# PowerPlan.net
KiCad netlist of a schematic drawn in Altium Designer
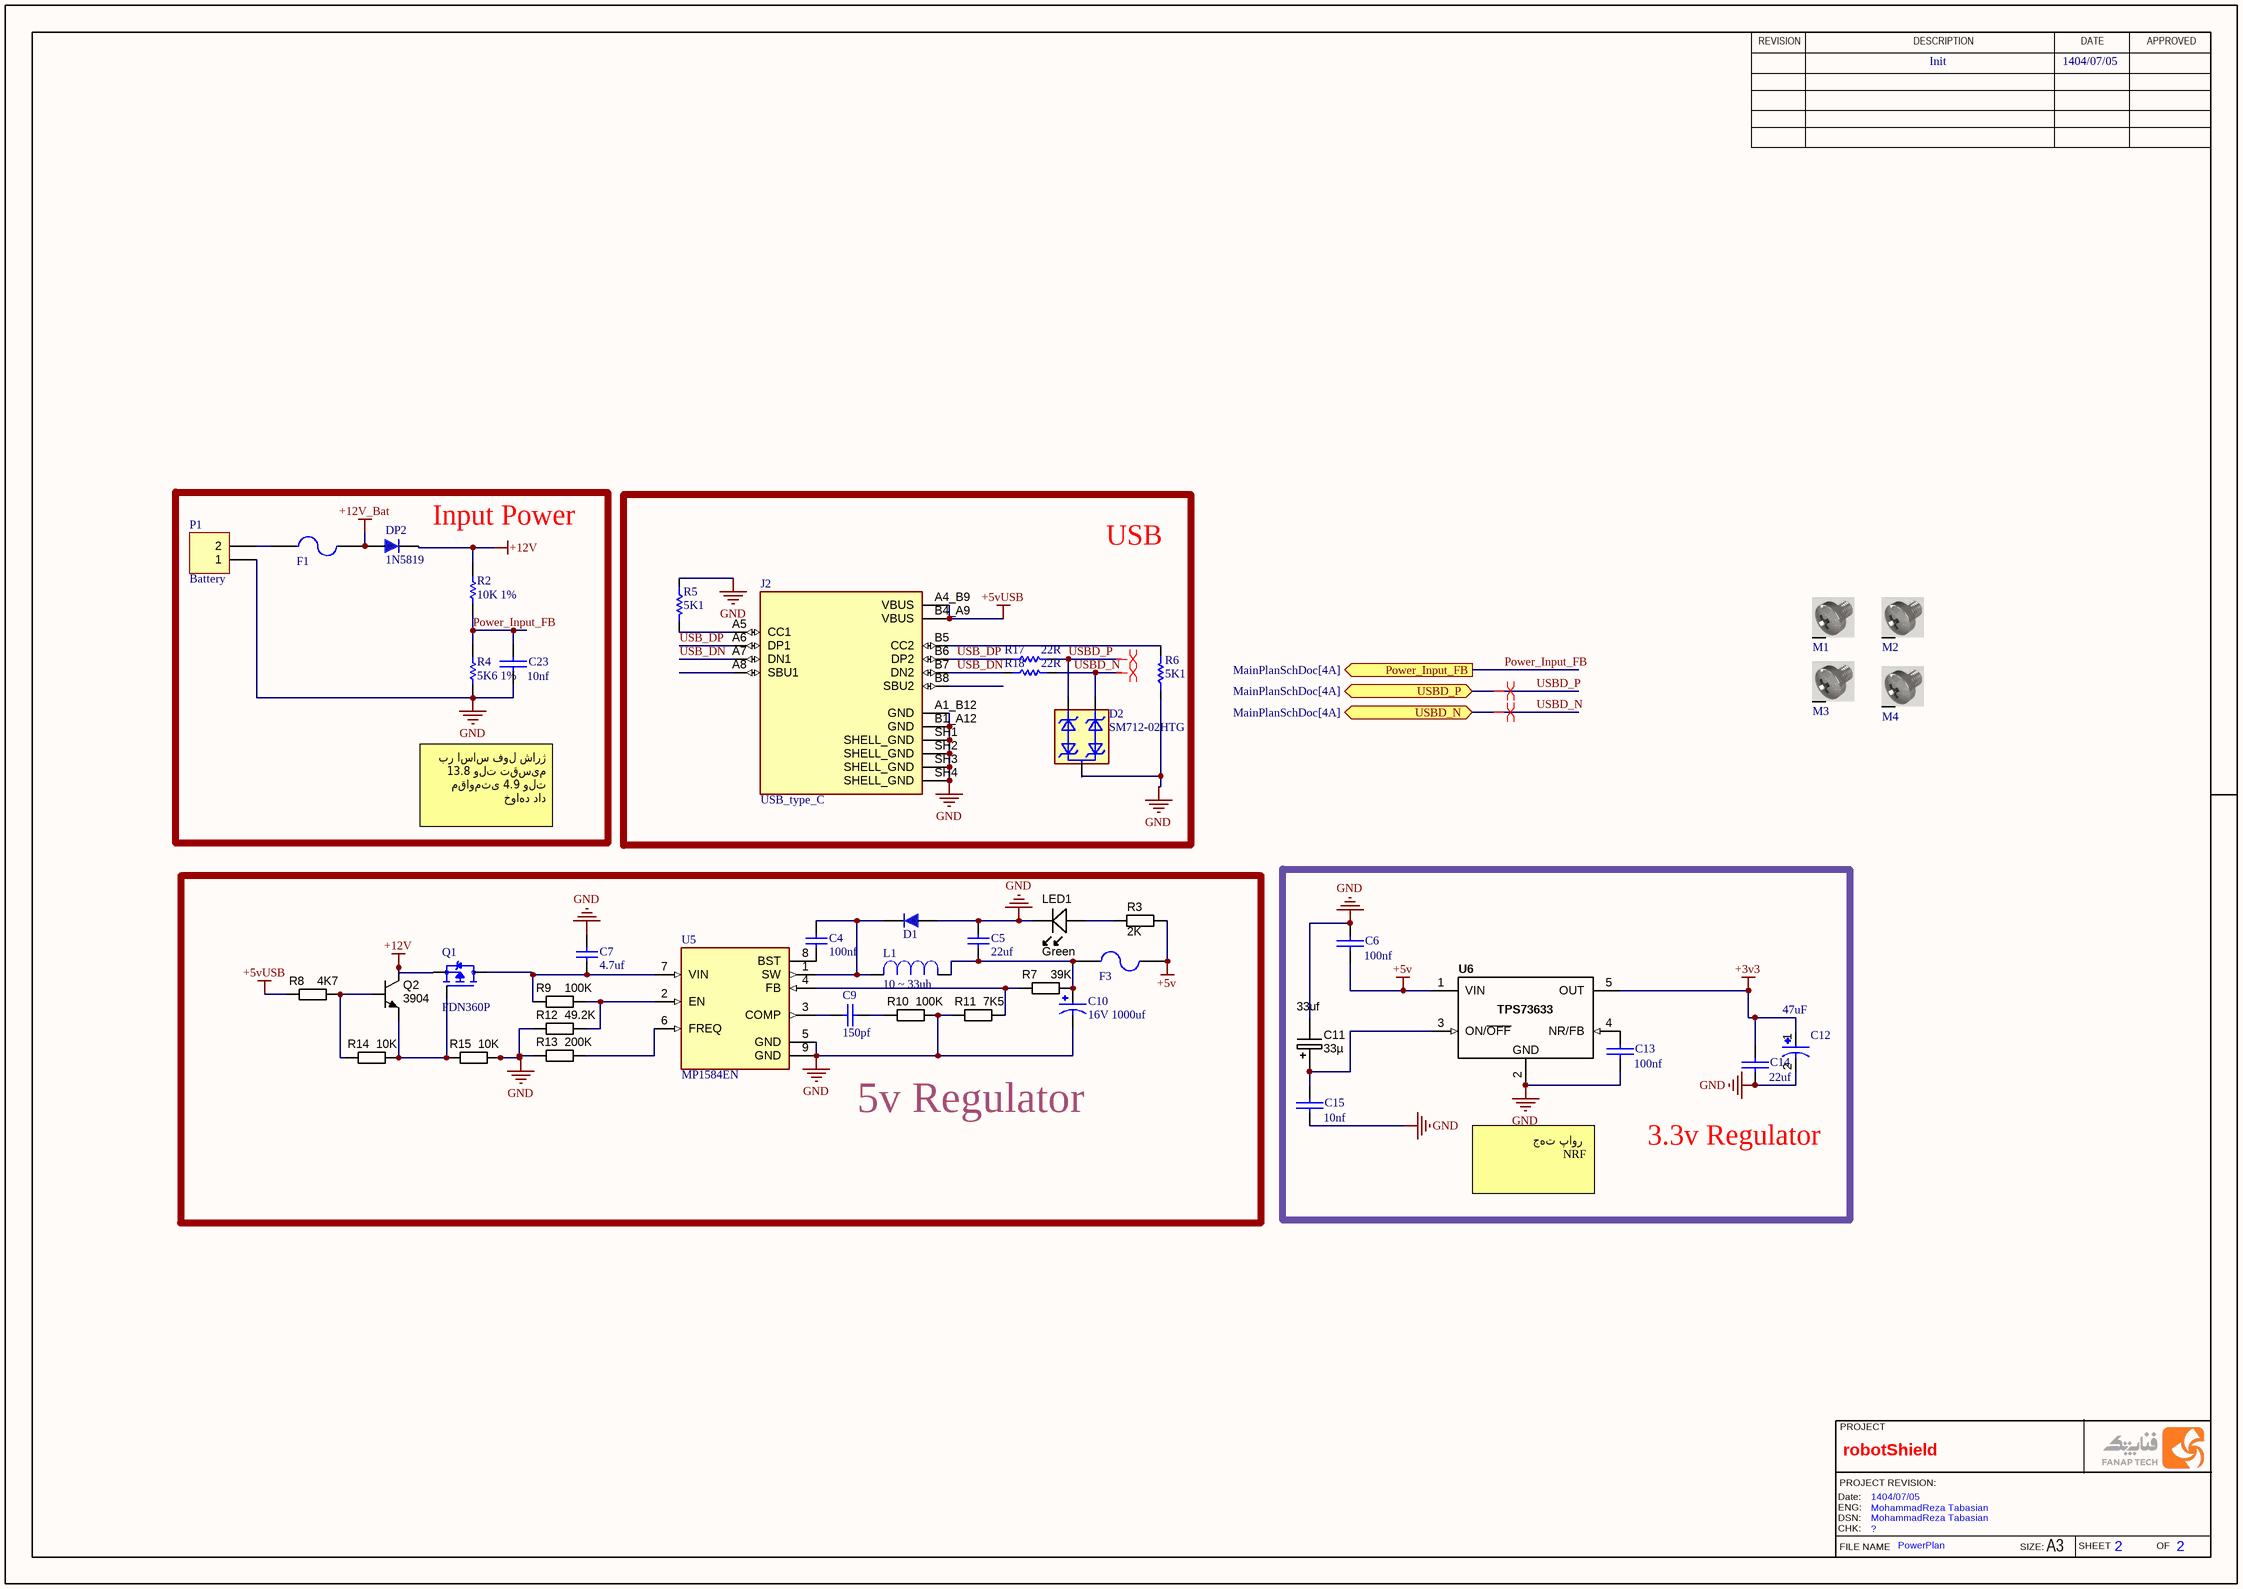
[diagram p0: PowerPlan.SchDoc]

(export (version "E")
  (design (tool "Eeschema 10.0.6"))
  (components
    (comp (ref "C4")
      (value "100nf")
      (footprint "C0805")
      (description "CAP 0805")
      (fields (field (name "DESIGNER") "Abbas Basereh"))
      (libsource (lib "Altium") (part "CAP SMD 0805"))
    )
    (comp (ref "C5")
      (value "22uf")
      (footprint "C1206")
      (description "CAP 1206")
      (fields (field (name "DESIGNER") "Abbas Basereh"))
      (libsource (lib "Altium") (part "CAP SMD 1206"))
    )
    (comp (ref "C6")
      (value "100nf")
      (footprint "C0805")
      (description "Bipolar Capacitor")
      (fields (field (name "VOLTAGE") "100V") (field (name "DESIGNER") "Saeid Jorablo"))
      (libsource (lib "My_Library") (part "Cap-Bipolar"))
    )
    (comp (ref "C7")
      (value "4.7uf")
      (footprint "C1206")
      (description "CAP 1206")
      (fields (field (name "DESIGNER") "Abbas Basereh"))
      (libsource (lib "Altium") (part "CAP SMD 1206"))
    )
    (comp (ref "C9")
      (value "150pf")
      (footprint "C0805")
      (description "CAP 0805")
      (fields (field (name "DESIGNER") "Abbas Basereh"))
      (libsource (lib "Altium") (part "CAP SMD 0805"))
    )
    (comp (ref "C10")
      (value "16V 1000uf")
      (footprint "CAP_SMD13*13")
      (description "CAP ALUM 470UF 20% 35V SMD")
      (fields (field (name "MF") "Panasonic Electronic Components") (field (name "MP") "EEE-FN1V471UP"))
      (libsource (lib "TB_LIB") (part "CAP_SMD13*13"))
    )
    (comp (ref "C11")
      (value "33uf")
      (footprint "CAPMP6032X280N")
      (description "Capacitor SMD Tantalum 33uF 10% 6.3V 3216-18")
      (fields (field (name "TOLERANCE") "±10%") (field (name "ALTIUM_VALUE") "33µ"))
      (libsource (lib "Utiliti_Library") (part "CAPT_33u_3216_6V3"))
    )
    (comp (ref "C12")
      (value "47uF")
      (footprint "CAPMP7343X430N")
      (description "Cap, Tant, 470uf, 10v, Case x")
      (fields (field (name "MP") "T541X107M025AH6510") (field (name "MF") "KEMET"))
      (libsource (lib "TB_LIB") (part "T541X107M025AH6510"))
    )
    (comp (ref "C13")
      (value "100nf")
      (footprint "C0805")
      (description "Bipolar Capacitor")
      (fields (field (name "VOLTAGE") "100V") (field (name "DESIGNER") "Saeid Jorablo"))
      (libsource (lib "My_Library") (part "Cap-Bipolar"))
    )
    (comp (ref "C14")
      (value "22uf")
      (footprint "C1206")
      (description "Bipolar Capacitor")
      (fields (field (name "VOLTAGE") "100V") (field (name "DESIGNER") "Saeid Jorablo"))
      (libsource (lib "My_Library") (part "Cap-Bipolar"))
    )
    (comp (ref "C15")
      (value "10nf")
      (footprint "C0805")
      (description "Bipolar Capacitor")
      (fields (field (name "VOLTAGE") "100V") (field (name "DESIGNER") "Saeid Jorablo"))
      (libsource (lib "My_Library") (part "Cap-Bipolar"))
    )
    (comp (ref "C23")
      (value "10nf")
      (footprint "C0805")
      (description "Bipolar Capacitor")
      (fields (field (name "VOLTAGE") "100V") (field (name "DESIGNER") "Saeid Jorablo"))
      (libsource (lib "My_Library") (part "Cap-Bipolar"))
    )
    (comp (ref "D1")
      (value "SS34")
      (footprint "DIOM4629X24N")
      (description "Standard Rectifiers")
      (fields (field (name "MANUFACTURER") "DC COMPONENTS") (field (name "DESIGNER") "Abbas Basereh"))
      (libsource (lib "Altium") (part "1n4007 SMD M7"))
    )
    (comp (ref "D2")
      (value "SM712-02HTG")
      (footprint "SOT23")
      (fields (field (name "MF") "Littelfuse"))
      (libsource (lib "TB_LIB") (part "SM712-02HTG"))
    )
    (comp (ref "DP2")
      (value "1N5819")
      (footprint "430X270D")
      (description "Schottkey Rectifiers")
      (fields (field (name "DESIGNER") "Abbas Basereh"))
      (libsource (lib "Altium") (part "1N5819"))
    )
    (comp (ref "F1")
      (value "F300ma")
      (footprint "1206 FUSE")
      (description "SMD Fuses 1206")
      (fields (field (name "DESIGNER") "Abbas Basereh"))
      (libsource (lib "Altium") (part "Fuse SMD1206"))
    )
    (comp (ref "F3")
      (value "F300ma")
      (footprint "1206 FUSE")
      (description "SMD Fuses 1206")
      (fields (field (name "DESIGNER") "Abbas Basereh"))
      (libsource (lib "Altium") (part "Fuse SMD1206"))
    )
    (comp (ref "J2")
      (value "USB_type_C")
      (footprint "USB_type_C")
      (fields (field (name "MF") "{'manufacturer': u'GCT'}") (field (name "MP") "USB4105-GF-A"))
      (libsource (lib "TB_LIB") (part "USB_type_C"))
    )
    (comp (ref "L1")
      (value "10 ~ 33uh")
      (footprint "IND_7*7")
      (description "100ÂµH Shielded Wirewound Inductor 1.96A 163mOhm Nonstandard")
      (fields (field (name "MF") "Eaton") (field (name "MP") "DR127-101-R"))
      (libsource (lib "TB_LIB") (part "Inductor 100uh"))
    )
    (comp (ref "LED1")
      (value "LED")
      (footprint "LED-0805-K")
      (description "LED, 0805 SMD, Green")
      (fields (field (name "COLOR") "Green"))
      (libsource (lib "Utiliti_Library") (part "LED_SMD_Green_0805_6mcd"))
    )
    (comp (ref "M1")
      (value "Screw")
      (footprint "Board Screw_No Silk")
      (description "Board Screw With Spacer")
      (libsource (lib "My Library") (part "Board Screw"))
    )
    (comp (ref "M2")
      (value "Screw")
      (footprint "Board Screw_No Silk")
      (description "Board Screw With Spacer")
      (libsource (lib "My Library") (part "Board Screw"))
    )
    (comp (ref "M3")
      (value "Screw")
      (footprint "Board Screw_No Silk")
      (description "Board Screw With Spacer")
      (libsource (lib "My Library") (part "Board Screw"))
    )
    (comp (ref "M4")
      (value "Screw")
      (footprint "Board Screw_No Silk")
      (description "Board Screw With Spacer")
      (libsource (lib "My Library") (part "Board Screw"))
    )
    (comp (ref "P1")
      (value "Battery")
      (footprint "HDR1X2")
      (description "Header, 2-Pin")
      (fields (field (name "PUBLISHER") "Altium Limited"))
      (libsource (lib "Altium") (part "Header 2"))
    )
    (comp (ref "Q1")
      (value "FDN360P")
      (footprint "SOT95P251X112-3N")
      (description "P-Channel 30V 2A (Ta) 500mW (Ta) Surface Mount SuperSOT-3")
      (fields (field (name "MF") "ON"))
      (libsource (lib "TB_LIB") (part "FDN360P"))
    )
    (comp (ref "Q2")
      (value "3904")
      (footprint "SOT23-3")
      (description "Transistor SMD NPN 40V 0.2A 250mW SOT-23")
      (fields (field (name "MANUFACTURER PART NUMBER 1") "3904"))
      (libsource (lib "Utiliti_Library") (part "NPN_MMBT3904"))
    )
    (comp (ref "R2")
      (value "10K 1%")
      (footprint "C0805")
      (description "RES 1206")
      (fields (field (name "DESIGNER") "Abbas Basereh"))
      (libsource (lib "2017AbbasBasereh9365731239 -ver1") (part "RES 1206 0.25W"))
    )
    (comp (ref "R3")
      (value "2K")
      (footprint "C0805")
      (description "Resistor SMD 0805")
      (libsource (lib "") (part "RES_0R_0805_1"))
    )
    (comp (ref "R4")
      (value "5K6 1%")
      (footprint "C0805")
      (description "RES 1206")
      (fields (field (name "DESIGNER") "Abbas Basereh"))
      (libsource (lib "2017AbbasBasereh9365731239 -ver1") (part "RES 1206 0.25W"))
    )
    (comp (ref "R5")
      (value "5K1")
      (footprint "C0805")
      (description "Resistor")
      (libsource (lib "My_Library") (part "Resistor"))
    )
    (comp (ref "R6")
      (value "5K1")
      (footprint "C0805")
      (description "Resistor")
      (libsource (lib "My_Library") (part "Resistor"))
    )
    (comp (ref "R7")
      (value "39K")
      (footprint "C0805")
      (description "Resistor SMD 0805")
      (libsource (lib "Utiliti_Library") (part "RES_0R_0805"))
    )
    (comp (ref "R8")
      (value "4K7")
      (footprint "C0805")
      (description "Resistor SMD 0805")
      (libsource (lib "Utiliti_Library") (part "RES_0R_0805"))
    )
    (comp (ref "R9")
      (value "100K")
      (footprint "C0805")
      (description "Resistor SMD 0805")
      (libsource (lib "Utiliti_Library") (part "RES_0R_0805"))
    )
    (comp (ref "R10")
      (value "100K")
      (footprint "C0805")
      (description "Resistor SMD 0805")
      (libsource (lib "Utiliti_Library") (part "RES_0R_0805"))
    )
    (comp (ref "R11")
      (value "7K5")
      (footprint "C0805")
      (description "Resistor SMD 0805")
      (libsource (lib "Utiliti_Library") (part "RES_0R_0805"))
    )
    (comp (ref "R12")
      (value "49.2K")
      (footprint "C0805")
      (description "Resistor SMD 0805")
      (libsource (lib "Utiliti_Library") (part "RES_0R_0805"))
    )
    (comp (ref "R13")
      (value "200K")
      (footprint "C0805")
      (description "Resistor SMD 0805")
      (libsource (lib "Utiliti_Library") (part "RES_0R_0805"))
    )
    (comp (ref "R14")
      (value "10K")
      (footprint "C0805")
      (description "Resistor SMD 0805")
      (libsource (lib "Utiliti_Library") (part "RES_0R_0805"))
    )
    (comp (ref "R15")
      (value "10K")
      (footprint "C0805")
      (description "Resistor SMD 0805")
      (libsource (lib "Utiliti_Library") (part "RES_0R_0805"))
    )
    (comp (ref "R17")
      (value "22R")
      (footprint "C0805")
      (description "Resistor")
      (libsource (lib "My_Library") (part "Resistor"))
    )
    (comp (ref "R18")
      (value "22R")
      (footprint "C0805")
      (description "Resistor")
      (libsource (lib "My_Library") (part "Resistor"))
    )
    (comp (ref "U5")
      (value "MP1584EN")
      (footprint "SOIC_8P_127P600X170-9N")
      (fields (field (name "MF") "Monolithic Power"))
      (libsource (lib "TB_LIB") (part "MP1584EN"))
    )
    (comp (ref "U6")
      (value "3.3V")
      (footprint "SOT23-5")
      (description "IC LDO Regulator 3.3V 400mA SOT23-5 SMD")
      (fields (field (name "TOLERANCE") "±0.5%"))
      (libsource (lib "Utiliti_Library") (part "LinREG_3V3_400mA_TPS73633DBV"))
    )
  )
  (nets
    (net (code "1") (name "+3v3") (class "Default")
      (node (ref "C12") (pin "1") (pinfunction "1_1") (pintype "passive"))
      (node (ref "C14") (pin "1") (pinfunction "+_1") (pintype "passive"))
      (node (ref "U6") (pin "5") (pinfunction "OUT_5") (pintype "power_in"))
    )
    (net (code "2") (name "+5v") (class "Default")
      (node (ref "C6") (pin "2") (pinfunction "-_2") (pintype "passive"))
      (node (ref "F3") (pin "2") (pinfunction "2_2") (pintype "passive"))
      (node (ref "R3") (pin "1") (pinfunction "1_1") (pintype "passive"))
      (node (ref "U6") (pin "1") (pinfunction "VIN_1") (pintype "power_in"))
    )
    (net (code "3") (name "+5vUSB") (class "Default")
      (node (ref "J2") (pin "A4_B9") (pinfunction "VBUS_A4_B9") (pintype "power_in"))
      (node (ref "J2") (pin "B4_A9") (pinfunction "VBUS_B4_A9") (pintype "power_in"))
      (node (ref "R8") (pin "1") (pinfunction "1_1") (pintype "passive"))
    )
    (net (code "4") (name "+12V") (class "Default")
      (node (ref "DP2") (pin "2") (pintype "passive"))
      (node (ref "Q1") (pin "2") (pinfunction "S_2") (pintype "passive"))
      (node (ref "Q2") (pin "3") (pinfunction "C_3") (pintype "passive"))
      (node (ref "R2") (pin "2") (pinfunction "2_2") (pintype "passive"))
    )
    (net (code "5") (name "+12V_Bat") (class "Default")
      (node (ref "DP2") (pin "1") (pintype "passive"))
      (node (ref "F1") (pin "2") (pinfunction "2_2") (pintype "passive"))
    )
    (net (code "6") (name "/Power_Input_FB") (class "Default")
      (node (ref "C23") (pin "1") (pinfunction "+_1") (pintype "passive"))
      (node (ref "R2") (pin "1") (pinfunction "1_1") (pintype "passive"))
      (node (ref "R4") (pin "2") (pinfunction "2_2") (pintype "passive"))
    )
    (net (code "7") (name "/USBD_N") (class "Default")
      (node (ref "D2") (pin "1") (pinfunction "1_1") (pintype "passive"))
      (node (ref "R18") (pin "2") (pinfunction "2_2") (pintype "passive"))
    )
    (net (code "8") (name "/USBD_P") (class "Default")
      (node (ref "D2") (pin "2") (pinfunction "2_2") (pintype "passive"))
      (node (ref "R17") (pin "2") (pinfunction "2_2") (pintype "passive"))
    )
    (net (code "9") (name "/USB_DN") (class "Default")
      (node (ref "J2") (pin "A7") (pinfunction "DN1_A7") (pintype "bidirectional"))
      (node (ref "J2") (pin "B7") (pinfunction "DN2_B7") (pintype "bidirectional"))
      (node (ref "R18") (pin "1") (pinfunction "1_1") (pintype "passive"))
    )
    (net (code "10") (name "/USB_DP") (class "Default")
      (node (ref "J2") (pin "A6") (pinfunction "DP1_A6") (pintype "bidirectional"))
      (node (ref "J2") (pin "B6") (pinfunction "DP2_B6") (pintype "bidirectional"))
      (node (ref "R17") (pin "1") (pinfunction "1_1") (pintype "passive"))
    )
    (net (code "11") (name "GND") (class "Default")
      (node (ref "C10") (pin "2") (pinfunction "2_2") (pintype "passive"))
      (node (ref "C11") (pin "2") (pintype "passive"))
      (node (ref "C12") (pin "2") (pinfunction "2_2") (pintype "passive"))
      (node (ref "C13") (pin "2") (pinfunction "-_2") (pintype "passive"))
      (node (ref "C14") (pin "2") (pinfunction "-_2") (pintype "passive"))
      (node (ref "C15") (pin "2") (pinfunction "-_2") (pintype "passive"))
      (node (ref "C23") (pin "2") (pinfunction "-_2") (pintype "passive"))
      (node (ref "C5") (pin "1") (pinfunction "1_1") (pintype "passive"))
      (node (ref "C6") (pin "1") (pinfunction "+_1") (pintype "passive"))
      (node (ref "C7") (pin "2") (pinfunction "2_2") (pintype "passive"))
      (node (ref "D1") (pin "1") (pintype "passive"))
      (node (ref "D2") (pin "3") (pinfunction "3_3") (pintype "passive"))
      (node (ref "J2") (pin "A1_B12") (pinfunction "GND_A1_B12") (pintype "power_in"))
      (node (ref "J2") (pin "B1_A12") (pinfunction "GND_B1_A12") (pintype "power_in"))
      (node (ref "J2") (pin "SH1") (pinfunction "SHELL_GND_SH1") (pintype "power_in"))
      (node (ref "J2") (pin "SH2") (pinfunction "SHELL_GND_SH2") (pintype "power_in"))
      (node (ref "J2") (pin "SH3") (pinfunction "SHELL_GND_SH3") (pintype "power_in"))
      (node (ref "J2") (pin "SH4") (pinfunction "SHELL_GND_SH4") (pintype "power_in"))
      (node (ref "LED1") (pin "K") (pinfunction "K_K") (pintype "passive"))
      (node (ref "P1") (pin "1") (pinfunction "1_1") (pintype "passive"))
      (node (ref "R10") (pin "2") (pinfunction "2_2") (pintype "passive"))
      (node (ref "R11") (pin "1") (pinfunction "1_1") (pintype "passive"))
      (node (ref "R12") (pin "1") (pinfunction "1_1") (pintype "passive"))
      (node (ref "R13") (pin "1") (pinfunction "1_1") (pintype "passive"))
      (node (ref "R15") (pin "2") (pinfunction "2_2") (pintype "passive"))
      (node (ref "R4") (pin "1") (pinfunction "1_1") (pintype "passive"))
      (node (ref "R5") (pin "1") (pinfunction "1_1") (pintype "passive"))
      (node (ref "R6") (pin "1") (pinfunction "1_1") (pintype "passive"))
      (node (ref "U5") (pin "5") (pinfunction "GND_5") (pintype "power_in"))
      (node (ref "U5") (pin "9") (pinfunction "GND_9") (pintype "power_in"))
      (node (ref "U6") (pin "2") (pinfunction "GND_2") (pintype "power_in"))
    )
    (net (code "12") (name "Net-(C9-Pad1)") (class "Default")
      (node (ref "C9") (pin "1") (pinfunction "1_1") (pintype "passive"))
      (node (ref "R10") (pin "1") (pinfunction "1_1") (pintype "passive"))
    )
    (net (code "13") (name "Net-(C10-Pad1)") (class "Default")
      (node (ref "C10") (pin "1") (pinfunction "1_1") (pintype "passive"))
      (node (ref "C5") (pin "2") (pinfunction "2_2") (pintype "passive"))
      (node (ref "F3") (pin "1") (pinfunction "1_1") (pintype "passive"))
      (node (ref "L1") (pin "1") (pinfunction "1_1") (pintype "passive"))
      (node (ref "R7") (pin "2") (pinfunction "2_2") (pintype "passive"))
    )
    (net (code "14") (name "Net-(C13-+)") (class "Default")
      (node (ref "C13") (pin "1") (pinfunction "+_1") (pintype "passive"))
      (node (ref "U6") (pin "4") (pinfunction "NR/FB_4") (pintype "input"))
    )
    (net (code "15") (name "Net-(C15-+)") (class "Default")
      (node (ref "C11") (pin "1") (pintype "passive"))
      (node (ref "C15") (pin "1") (pinfunction "+_1") (pintype "passive"))
      (node (ref "U6") (pin "3") (pinfunction "ON/~{OFF}_3") (pintype "input"))
    )
    (net (code "16") (name "Net-(F1-Pad1)") (class "Default")
      (node (ref "F1") (pin "1") (pinfunction "1_1") (pintype "passive"))
      (node (ref "P1") (pin "2") (pinfunction "2_2") (pintype "passive"))
    )
    (net (code "17") (name "Net-(J2-CC1)") (class "Default")
      (node (ref "J2") (pin "A5") (pinfunction "CC1_A5") (pintype "bidirectional"))
      (node (ref "R5") (pin "2") (pinfunction "2_2") (pintype "passive"))
    )
    (net (code "18") (name "Net-(J2-CC2)") (class "Default")
      (node (ref "J2") (pin "B5") (pinfunction "CC2_B5") (pintype "bidirectional"))
      (node (ref "R6") (pin "2") (pinfunction "2_2") (pintype "passive"))
    )
    (net (code "19") (name "Net-(LED1-PadA)") (class "Default")
      (node (ref "LED1") (pin "A") (pinfunction "A_A") (pintype "passive"))
      (node (ref "R3") (pin "2") (pinfunction "2_2") (pintype "passive"))
    )
    (net (code "20") (name "Net-(Q1-D)") (class "Default")
      (node (ref "C7") (pin "1") (pinfunction "1_1") (pintype "passive"))
      (node (ref "Q1") (pin "3") (pinfunction "D_3") (pintype "passive"))
      (node (ref "R9") (pin "1") (pinfunction "1_1") (pintype "passive"))
      (node (ref "U5") (pin "7") (pinfunction "VIN_7") (pintype "input"))
    )
    (net (code "21") (name "Net-(Q1-G)") (class "Default")
      (node (ref "Q1") (pin "1") (pinfunction "G_1") (pintype "passive"))
      (node (ref "Q2") (pin "2") (pinfunction "E_2") (pintype "passive"))
      (node (ref "R14") (pin "2") (pinfunction "2_2") (pintype "passive"))
      (node (ref "R15") (pin "1") (pinfunction "1_1") (pintype "passive"))
    )
    (net (code "22") (name "Net-(Q2-B)") (class "Default")
      (node (ref "Q2") (pin "1") (pinfunction "B_1") (pintype "passive"))
      (node (ref "R14") (pin "1") (pinfunction "1_1") (pintype "passive"))
      (node (ref "R8") (pin "2") (pinfunction "2_2") (pintype "passive"))
    )
    (net (code "23") (name "Net-(U5-BST)") (class "Default")
      (node (ref "C4") (pin "2") (pinfunction "2_2") (pintype "passive"))
      (node (ref "U5") (pin "8") (pinfunction "BST_8") (pintype "passive"))
    )
    (net (code "24") (name "Net-(U5-COMP)") (class "Default")
      (node (ref "C9") (pin "2") (pinfunction "2_2") (pintype "passive"))
      (node (ref "U5") (pin "3") (pinfunction "COMP_3") (pintype "output"))
    )
    (net (code "25") (name "Net-(U5-EN)") (class "Default")
      (node (ref "R12") (pin "2") (pinfunction "2_2") (pintype "passive"))
      (node (ref "R9") (pin "2") (pinfunction "2_2") (pintype "passive"))
      (node (ref "U5") (pin "2") (pinfunction "EN_2") (pintype "input"))
    )
    (net (code "26") (name "Net-(U5-FB)") (class "Default")
      (node (ref "R11") (pin "2") (pinfunction "2_2") (pintype "passive"))
      (node (ref "R7") (pin "1") (pinfunction "1_1") (pintype "passive"))
      (node (ref "U5") (pin "4") (pinfunction "FB_4") (pintype "input"))
    )
    (net (code "27") (name "Net-(U5-FREQ)") (class "Default")
      (node (ref "R13") (pin "2") (pinfunction "2_2") (pintype "passive"))
      (node (ref "U5") (pin "6") (pinfunction "FREQ_6") (pintype "input"))
    )
    (net (code "28") (name "Net-(U5-SW)") (class "Default")
      (node (ref "C4") (pin "1") (pinfunction "1_1") (pintype "passive"))
      (node (ref "D1") (pin "2") (pintype "passive"))
      (node (ref "L1") (pin "2") (pinfunction "2_2") (pintype "passive"))
      (node (ref "U5") (pin "1") (pinfunction "SW_1") (pintype "output"))
    )
    (net (code "29") (name "unconnected-(J2-SBU1-PadA8)") (class "Default")
      (node (ref "J2") (pin "A8") (pinfunction "SBU1_A8") (pintype "bidirectional"))
    )
    (net (code "30") (name "unconnected-(J2-SBU2-PadB8)") (class "Default")
      (node (ref "J2") (pin "B8") (pinfunction "SBU2_B8") (pintype "bidirectional"))
    )
    (net (code "31") (name "unconnected-(M1-PadS)") (class "Default")
      (node (ref "M1") (pin "S") (pinfunction "S_S") (pintype "passive"))
    )
    (net (code "32") (name "unconnected-(M2-PadS)") (class "Default")
      (node (ref "M2") (pin "S") (pinfunction "S_S") (pintype "passive"))
    )
    (net (code "33") (name "unconnected-(M3-PadS)") (class "Default")
      (node (ref "M3") (pin "S") (pinfunction "S_S") (pintype "passive"))
    )
    (net (code "34") (name "unconnected-(M4-PadS)") (class "Default")
      (node (ref "M4") (pin "S") (pinfunction "S_S") (pintype "passive"))
    )
  )
)
